# pwm.net
KiCad netlist of a schematic drawn in Altium Designer
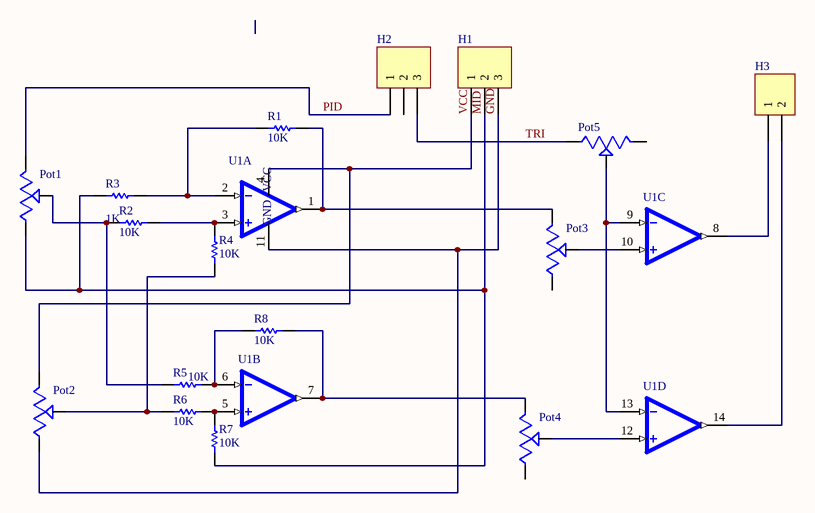
[diagram p0: pwm.SchDoc]

(export (version "E")
  (design (tool "Eeschema 10.0.6"))
  (components
    (comp (ref "H1")
      (value "Header 3")
      (footprint "HDR1X3")
      (description "Header, 3-Pin")
      (fields (field (name "PUBLISHER") "Altium Limited"))
      (libsource (lib "Miscellaneous Connectors") (part "Header 3"))
    )
    (comp (ref "H2")
      (value "Header 3")
      (footprint "HDR1X3")
      (description "Header, 3-Pin")
      (fields (field (name "PUBLISHER") "Altium Limited"))
      (libsource (lib "Miscellaneous Connectors") (part "Header 3"))
    )
    (comp (ref "H3")
      (value "Header 2")
      (footprint "HDR1X2")
      (description "Header, 2-Pin")
      (fields (field (name "PUBLISHER") "Altium Limited"))
      (libsource (lib "Miscellaneous Connectors") (part "Header 2"))
    )
    (comp (ref "Pot1")
      (value "3266W-1-103")
      (footprint "TRIM_3266W-1-103")
      (description "10 kOhms 0.25W, 1/4W PC Pins Through Hole Trimmer Potentiometer Cermet 12 Turn Top Adjustment")
      (fields (field (name "MF") "Bourns"))
      (libsource (lib "3266W-1-103") (part "3266W-1-103"))
    )
    (comp (ref "Pot2")
      (value "3266W-1-103")
      (footprint "TRIM_3266W-1-103")
      (description "10 kOhms 0.25W, 1/4W PC Pins Through Hole Trimmer Potentiometer Cermet 12 Turn Top Adjustment")
      (fields (field (name "MF") "Bourns"))
      (libsource (lib "3266W-1-103") (part "3266W-1-103"))
    )
    (comp (ref "Pot3")
      (value "3266W-1-103")
      (footprint "TRIM_3266W-1-103")
      (description "10 kOhms 0.25W, 1/4W PC Pins Through Hole Trimmer Potentiometer Cermet 12 Turn Top Adjustment")
      (fields (field (name "MF") "Bourns"))
      (libsource (lib "3266W-1-103") (part "3266W-1-103"))
    )
    (comp (ref "Pot4")
      (value "3266W-1-103")
      (footprint "TRIM_3266W-1-103")
      (description "10 kOhms 0.25W, 1/4W PC Pins Through Hole Trimmer Potentiometer Cermet 12 Turn Top Adjustment")
      (fields (field (name "MF") "Bourns"))
      (libsource (lib "3266W-1-103") (part "3266W-1-103"))
    )
    (comp (ref "Pot5")
      (value "3266W-1-103")
      (footprint "TRIM_3266W-1-103")
      (description "10 kOhms 0.25W, 1/4W PC Pins Through Hole Trimmer Potentiometer Cermet 12 Turn Top Adjustment")
      (fields (field (name "MF") "Bourns"))
      (libsource (lib "3266W-1-103") (part "3266W-1-103"))
    )
    (comp (ref "R1")
      (value "10K")
      (footprint "AXIAL-0.3")
      (fields (field (name "PUBLISHER") "Altium Limited"))
      (libsource (lib "Miscellaneous Devices") (part "Res1"))
    )
    (comp (ref "R2")
      (value "10K")
      (footprint "AXIAL-0.3")
      (description "Resistor")
      (fields (field (name "PUBLISHER") "Altium Limited"))
      (libsource (lib "Miscellaneous Devices") (part "Res1"))
    )
    (comp (ref "R3")
      (value "1K")
      (footprint "AXIAL-0.3")
      (description "Resistor")
      (fields (field (name "Comment") "Res1") (field (name "PUBLISHER") "Altium Limited"))
      (libsource (lib "Miscellaneous Devices") (part "Res1"))
    )
    (comp (ref "R4")
      (value "10K")
      (footprint "AXIAL-0.3")
      (description "Resistor")
      (fields (field (name "PUBLISHER") "Altium Limited"))
      (libsource (lib "Miscellaneous Devices") (part "Res1"))
    )
    (comp (ref "R5")
      (value "10K")
      (footprint "AXIAL-0.3")
      (description "Resistor")
      (fields (field (name "PUBLISHER") "Altium Limited"))
      (libsource (lib "Miscellaneous Devices") (part "Res1"))
    )
    (comp (ref "R6")
      (value "10K")
      (footprint "AXIAL-0.3")
      (description "Resistor")
      (fields (field (name "PUBLISHER") "Altium Limited"))
      (libsource (lib "Miscellaneous Devices") (part "Res1"))
    )
    (comp (ref "R7")
      (value "10K")
      (footprint "AXIAL-0.3")
      (description "Resistor")
      (fields (field (name "PUBLISHER") "Altium Limited"))
      (libsource (lib "Miscellaneous Devices") (part "Res1"))
    )
    (comp (ref "R8")
      (value "10K")
      (footprint "AXIAL-0.3")
      (description "Resistor")
      (fields (field (name "PUBLISHER") "Altium Limited"))
      (libsource (lib "Miscellaneous Devices") (part "Res1"))
    )
    (comp (ref "U1")
      (value "LM324NE3")
      (footprint "DIP794W45P254L1969H508Q14")
      (description "Quad, 30-V, 1.2-MHz operational amplifier")
      (fields (field (name "MF") "Texas Instruments"))
      (libsource (lib "LM324NE3") (part "LM324NE3"))
    )
  )
  (nets
    (net (code "1") (name "/GND") (class "Default")
      (node (ref "H1") (pin "3") (pinfunction "3_3") (pintype "passive"))
      (node (ref "Pot2") (pin "1") (pinfunction "CCW_1") (pintype "passive"))
      (node (ref "U1") (pin "11") (pinfunction "GND_11") (pintype "power_in"))
    )
    (net (code "2") (name "/MID") (class "Default")
      (node (ref "H1") (pin "2") (pinfunction "2_2") (pintype "passive"))
      (node (ref "Pot1") (pin "1") (pinfunction "CCW_1") (pintype "passive"))
      (node (ref "R3") (pin "1") (pinfunction "1_1") (pintype "passive"))
      (node (ref "R7") (pin "1") (pinfunction "1_1") (pintype "passive"))
    )
    (net (code "3") (name "/PID") (class "Default")
      (node (ref "H2") (pin "1") (pinfunction "1_1") (pintype "passive"))
      (node (ref "Pot1") (pin "3") (pinfunction "CW_3") (pintype "passive"))
    )
    (net (code "4") (name "/TRI") (class "Default")
      (node (ref "H2") (pin "3") (pinfunction "3_3") (pintype "passive"))
      (node (ref "Pot5") (pin "1") (pinfunction "CCW_1") (pintype "passive"))
    )
    (net (code "5") (name "/VCC") (class "Default")
      (node (ref "H1") (pin "1") (pinfunction "1_1") (pintype "passive"))
      (node (ref "Pot2") (pin "3") (pinfunction "CW_3") (pintype "passive"))
      (node (ref "U1") (pin "4") (pinfunction "VCC_4") (pintype "power_in"))
    )
    (net (code "6") (name "Net-(Pot1-WIPER)") (class "Default")
      (node (ref "Pot1") (pin "2") (pinfunction "WIPER_2") (pintype "passive"))
      (node (ref "R2") (pin "2") (pinfunction "2_2") (pintype "passive"))
      (node (ref "R5") (pin "2") (pinfunction "2_2") (pintype "passive"))
    )
    (net (code "7") (name "Net-(Pot2-WIPER)") (class "Default")
      (node (ref "Pot2") (pin "2") (pinfunction "WIPER_2") (pintype "passive"))
      (node (ref "R4") (pin "2") (pinfunction "2_2") (pintype "passive"))
      (node (ref "R6") (pin "2") (pinfunction "2_2") (pintype "passive"))
    )
    (net (code "8") (name "Net-(Pot3-CW)") (class "Default")
      (node (ref "Pot3") (pin "3") (pinfunction "CW_3") (pintype "passive"))
      (node (ref "R1") (pin "2") (pinfunction "2_2") (pintype "passive"))
      (node (ref "U1") (pin "1") (pinfunction "1OUT_1") (pintype "output"))
    )
    (net (code "9") (name "Net-(Pot3-WIPER)") (class "Default")
      (node (ref "Pot3") (pin "2") (pinfunction "WIPER_2") (pintype "passive"))
      (node (ref "U1") (pin "10") (pinfunction "3IN+_10") (pintype "input"))
    )
    (net (code "10") (name "Net-(Pot4-CW)") (class "Default")
      (node (ref "Pot4") (pin "3") (pinfunction "CW_3") (pintype "passive"))
      (node (ref "R8") (pin "2") (pinfunction "2_2") (pintype "passive"))
      (node (ref "U1") (pin "7") (pinfunction "2OUT_7") (pintype "output"))
    )
    (net (code "11") (name "Net-(Pot4-WIPER)") (class "Default")
      (node (ref "Pot4") (pin "2") (pinfunction "WIPER_2") (pintype "passive"))
      (node (ref "U1") (pin "12") (pinfunction "4IN+_12") (pintype "input"))
    )
    (net (code "12") (name "Net-(Pot5-WIPER)") (class "Default")
      (node (ref "Pot5") (pin "2") (pinfunction "WIPER_2") (pintype "passive"))
      (node (ref "U1") (pin "13") (pinfunction "4IN-_13") (pintype "input"))
      (node (ref "U1") (pin "9") (pinfunction "3IN-_9") (pintype "input"))
    )
    (net (code "13") (name "Net-(U1A-1IN+)") (class "Default")
      (node (ref "R2") (pin "1") (pinfunction "1_1") (pintype "passive"))
      (node (ref "R4") (pin "1") (pinfunction "1_1") (pintype "passive"))
      (node (ref "U1") (pin "3") (pinfunction "1IN+_3") (pintype "input"))
    )
    (net (code "14") (name "Net-(U1A-1IN-)") (class "Default")
      (node (ref "R1") (pin "1") (pinfunction "1_1") (pintype "passive"))
      (node (ref "R3") (pin "2") (pinfunction "2_2") (pintype "passive"))
      (node (ref "U1") (pin "2") (pinfunction "1IN-_2") (pintype "input"))
    )
    (net (code "15") (name "Net-(U1B-2IN+)") (class "Default")
      (node (ref "R6") (pin "1") (pinfunction "1_1") (pintype "passive"))
      (node (ref "R7") (pin "2") (pinfunction "2_2") (pintype "passive"))
      (node (ref "U1") (pin "5") (pinfunction "2IN+_5") (pintype "input"))
    )
    (net (code "16") (name "Net-(U1B-2IN-)") (class "Default")
      (node (ref "R5") (pin "1") (pinfunction "1_1") (pintype "passive"))
      (node (ref "R8") (pin "1") (pinfunction "1_1") (pintype "passive"))
      (node (ref "U1") (pin "6") (pinfunction "2IN-_6") (pintype "input"))
    )
    (net (code "17") (name "Net-(U1C-3OUT)") (class "Default")
      (node (ref "H3") (pin "1") (pinfunction "1_1") (pintype "passive"))
      (node (ref "U1") (pin "8") (pinfunction "3OUT_8") (pintype "output"))
    )
    (net (code "18") (name "Net-(U1D-4OUT)") (class "Default")
      (node (ref "H3") (pin "2") (pinfunction "2_2") (pintype "passive"))
      (node (ref "U1") (pin "14") (pinfunction "4OUT_14") (pintype "output"))
    )
    (net (code "19") (name "unconnected-(H2-Pad2)") (class "Default")
      (node (ref "H2") (pin "2") (pinfunction "2_2") (pintype "passive"))
    )
    (net (code "20") (name "unconnected-(Pot3-CCW-Pad1)") (class "Default")
      (node (ref "Pot3") (pin "1") (pinfunction "CCW_1") (pintype "passive"))
    )
    (net (code "21") (name "unconnected-(Pot4-CCW-Pad1)") (class "Default")
      (node (ref "Pot4") (pin "1") (pinfunction "CCW_1") (pintype "passive"))
    )
    (net (code "22") (name "unconnected-(Pot5-CW-Pad3)") (class "Default")
      (node (ref "Pot5") (pin "3") (pinfunction "CW_3") (pintype "passive"))
    )
  )
)
